# Electronic_Synchronized_Fireflies.net
KiCad netlist of a schematic drawn in EAGLE
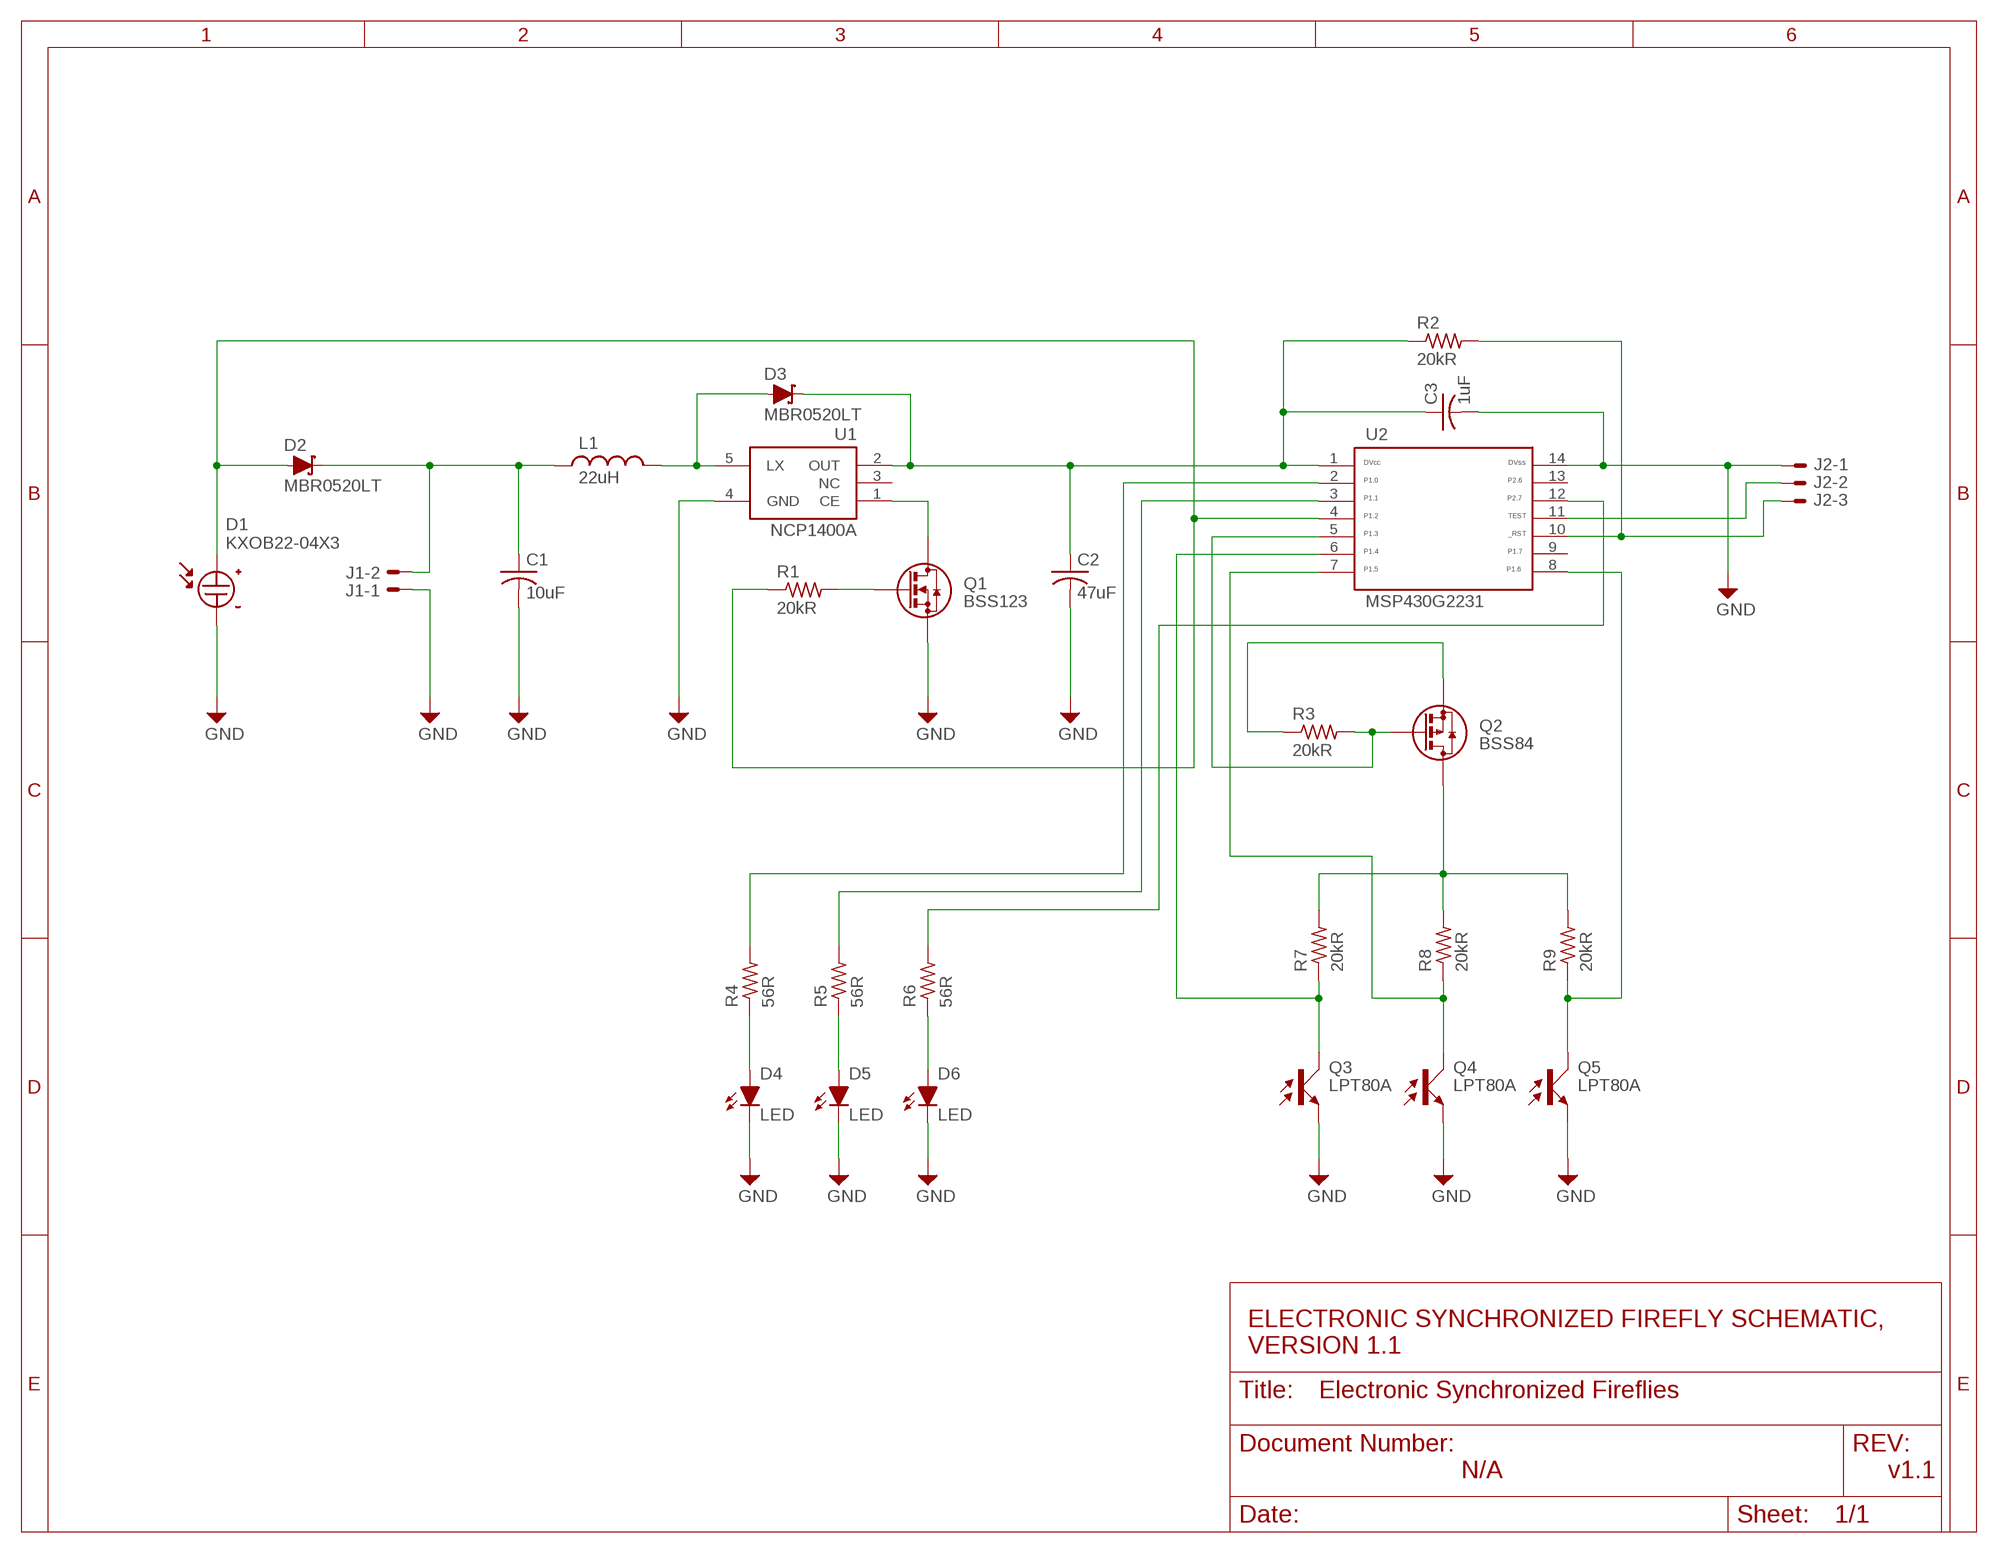
[diagram p0: schematic, sheet 1]

(export (version "E")
  (design (tool "Eeschema 10.0.6"))
  (components
    (comp (ref "C1")
      (value "10uF")
      (footprint "eagle-import:CAPACITOR_0805")
      (libsource (lib "eagle-import") (part "CAPACITOR"))
    )
    (comp (ref "C2")
      (value "47uF")
      (footprint "eagle-import:CAPACITOR_0805")
      (libsource (lib "eagle-import") (part "CAPACITOR"))
    )
    (comp (ref "C3")
      (value "1uF")
      (footprint "eagle-import:CAPACITOR_0805")
      (libsource (lib "eagle-import") (part "CAPACITOR"))
    )
    (comp (ref "D1")
      (value "KXOB22-04X3")
      (footprint "eagle-import:KXOB22-04X3")
      (libsource (lib "eagle-import") (part "KXOB22-04X3"))
    )
    (comp (ref "D2")
      (value "MBR0520LT")
      (footprint "eagle-import:SOD123")
      (libsource (lib "eagle-import") (part "MBR0520LT"))
    )
    (comp (ref "D3")
      (value "MBR0520LT")
      (footprint "eagle-import:SOD123")
      (libsource (lib "eagle-import") (part "MBR0520LT"))
    )
    (comp (ref "D4")
      (value "LED")
      (footprint "eagle-import:LED5MMRT")
      (libsource (lib "eagle-import") (part "LEDRTANGLEHOLDER"))
    )
    (comp (ref "D5")
      (value "LED")
      (footprint "eagle-import:LED5MMRT")
      (libsource (lib "eagle-import") (part "LEDRTANGLEHOLDER"))
    )
    (comp (ref "D6")
      (value "LED")
      (footprint "eagle-import:LED5MMRT")
      (libsource (lib "eagle-import") (part "LEDRTANGLEHOLDER"))
    )
    (comp (ref "FRAME1")
      (value "FRAME_A_L")
      (footprint "eagle-import:FRAME_A_L")
      (libsource (lib "eagle-import") (part "FRAME_A_L"))
    )
    (comp (ref "J1")
      (value "2WIRE_HEADER")
      (footprint "eagle-import:2WIRE_HEADER")
      (fields (field (name "MF") "MOLEX") (field (name "MPN") "22-23-2021"))
      (libsource (lib "eagle-import") (part "2WIRE_HEADER"))
    )
    (comp (ref "J2")
      (value "3WIRE_HEADER")
      (footprint "eagle-import:3WIRE_HEADER")
      (fields (field (name "MF") "MOLEX") (field (name "MPN") "22-23-2031"))
      (libsource (lib "eagle-import") (part "3WIRE_HEADER"))
    )
    (comp (ref "L1")
      (value "22uH")
      (footprint "eagle-import:INDUCTOR_1007")
      (libsource (lib "eagle-import") (part "INDUCTOR"))
    )
    (comp (ref "Q1")
      (value "BSS123")
      (footprint "eagle-import:SOT23")
      (libsource (lib "eagle-import") (part "BSS123"))
    )
    (comp (ref "Q2")
      (value "BSS84")
      (footprint "eagle-import:SOT23")
      (libsource (lib "eagle-import") (part "BSS84"))
    )
    (comp (ref "Q3")
      (value "LPT80A")
      (footprint "eagle-import:LED5MMRT")
      (libsource (lib "eagle-import") (part "LPT80ARTANGLEHOLDER"))
    )
    (comp (ref "Q4")
      (value "LPT80A")
      (footprint "eagle-import:LED5MMRT")
      (libsource (lib "eagle-import") (part "LPT80ARTANGLEHOLDER"))
    )
    (comp (ref "Q5")
      (value "LPT80A")
      (footprint "eagle-import:LED5MMRT")
      (libsource (lib "eagle-import") (part "LPT80ARTANGLEHOLDER"))
    )
    (comp (ref "R1")
      (value "20kR")
      (footprint "eagle-import:RESISTOR_0805")
      (libsource (lib "eagle-import") (part "RESISTOR"))
    )
    (comp (ref "R2")
      (value "20kR")
      (footprint "eagle-import:RESISTOR_0805")
      (libsource (lib "eagle-import") (part "RESISTOR"))
    )
    (comp (ref "R3")
      (value "20kR")
      (footprint "eagle-import:RESISTOR_0805")
      (libsource (lib "eagle-import") (part "RESISTOR"))
    )
    (comp (ref "R4")
      (value "56R")
      (footprint "eagle-import:RESISTOR_0805")
      (libsource (lib "eagle-import") (part "RESISTOR"))
    )
    (comp (ref "R5")
      (value "56R")
      (footprint "eagle-import:RESISTOR_0805")
      (libsource (lib "eagle-import") (part "RESISTOR"))
    )
    (comp (ref "R6")
      (value "56R")
      (footprint "eagle-import:RESISTOR_0805")
      (libsource (lib "eagle-import") (part "RESISTOR"))
    )
    (comp (ref "R7")
      (value "20kR")
      (footprint "eagle-import:RESISTOR_0805")
      (libsource (lib "eagle-import") (part "RESISTOR"))
    )
    (comp (ref "R8")
      (value "20kR")
      (footprint "eagle-import:RESISTOR_0805")
      (libsource (lib "eagle-import") (part "RESISTOR"))
    )
    (comp (ref "R9")
      (value "20kR")
      (footprint "eagle-import:RESISTOR_0805")
      (libsource (lib "eagle-import") (part "RESISTOR"))
    )
    (comp (ref "U$1")
      (value "DOCFIELD")
      (footprint "eagle-import:DOCFIELD")
      (libsource (lib "eagle-import") (part "DOCFIELD"))
    )
    (comp (ref "U1")
      (value "NCP1400A")
      (footprint "eagle-import:SOT23-5")
      (libsource (lib "eagle-import") (part "NCP1400A"))
    )
    (comp (ref "U2")
      (value "MSP430G2231")
      (footprint "eagle-import:TSSOP-14")
      (libsource (lib "eagle-import") (part "MSP430G2231"))
    )
  )
  (nets
    (net (code "1") (name "GND") (class "Default")
      (node (ref "C1") (pin "2") (pinfunction "2_2") (pintype "passive"))
      (node (ref "C2") (pin "2") (pinfunction "2_2") (pintype "passive"))
      (node (ref "C3") (pin "2") (pinfunction "2_2") (pintype "passive"))
      (node (ref "D1") (pin "P$2") (pinfunction "-_P$2") (pintype "passive"))
      (node (ref "D4") (pin "K") (pinfunction "C_K") (pintype "passive"))
      (node (ref "D5") (pin "K") (pinfunction "C_K") (pintype "passive"))
      (node (ref "D6") (pin "K") (pinfunction "C_K") (pintype "passive"))
      (node (ref "J1") (pin "1") (pinfunction "S_1") (pintype "passive"))
      (node (ref "J2") (pin "1") (pinfunction "S_1") (pintype "passive"))
      (node (ref "Q1") (pin "3") (pinfunction "D_3") (pintype "passive"))
      (node (ref "Q3") (pin "K") (pinfunction "E_K") (pintype "passive"))
      (node (ref "Q4") (pin "K") (pinfunction "E_K") (pintype "passive"))
      (node (ref "Q5") (pin "K") (pinfunction "E_K") (pintype "passive"))
      (node (ref "U1") (pin "4") (pinfunction "GND_4") (pintype "bidirectional"))
      (node (ref "U2") (pin "14") (pinfunction "14_14") (pintype "bidirectional"))
    )
    (net (code "2") (name "Net-(D1-+)") (class "Default")
      (node (ref "D1") (pin "P$1") (pinfunction "+_P$1") (pintype "passive"))
      (node (ref "D2") (pin "A") (pinfunction "A_A") (pintype "input"))
      (node (ref "R1") (pin "1") (pinfunction "P$1_1") (pintype "passive"))
      (node (ref "U2") (pin "4") (pinfunction "4_4") (pintype "bidirectional"))
    )
    (net (code "3") (name "Net-(J1B-S)") (class "Default")
      (node (ref "C1") (pin "1") (pinfunction "1_1") (pintype "passive"))
      (node (ref "D2") (pin "C") (pinfunction "C_C") (pintype "output"))
      (node (ref "J1") (pin "2") (pinfunction "S_2") (pintype "passive"))
      (node (ref "L1") (pin "P$1") (pinfunction "1_P$1") (pintype "passive"))
    )
    (net (code "4") (name "Net-(J2B-S)") (class "Default")
      (node (ref "J2") (pin "2") (pinfunction "S_2") (pintype "passive"))
      (node (ref "U2") (pin "11") (pinfunction "11_11") (pintype "bidirectional"))
    )
    (net (code "5") (name "Net-(J2C-S)") (class "Default")
      (node (ref "J2") (pin "3") (pinfunction "S_3") (pintype "passive"))
      (node (ref "R2") (pin "2") (pinfunction "P$2_2") (pintype "passive"))
      (node (ref "U2") (pin "10") (pinfunction "10_10") (pintype "bidirectional"))
    )
    (net (code "6") (name "Net-(L1-2)") (class "Default")
      (node (ref "D3") (pin "A") (pinfunction "A_A") (pintype "input"))
      (node (ref "L1") (pin "P$2") (pinfunction "2_P$2") (pintype "passive"))
      (node (ref "U1") (pin "5") (pinfunction "LX_5") (pintype "bidirectional"))
    )
    (net (code "7") (name "Net-(Q1-G)") (class "Default")
      (node (ref "Q1") (pin "1") (pinfunction "G_1") (pintype "passive"))
      (node (ref "R1") (pin "2") (pinfunction "P$2_2") (pintype "passive"))
    )
    (net (code "8") (name "Net-(Q1-S)") (class "Default")
      (node (ref "Q1") (pin "2") (pinfunction "S_2") (pintype "passive"))
      (node (ref "U1") (pin "1") (pinfunction "CE_1") (pintype "bidirectional"))
    )
    (net (code "9") (name "Net-(Q2-D)") (class "Default")
      (node (ref "Q2") (pin "3") (pinfunction "D_3") (pintype "passive"))
      (node (ref "R7") (pin "2") (pinfunction "P$2_2") (pintype "passive"))
      (node (ref "R8") (pin "2") (pinfunction "P$2_2") (pintype "passive"))
      (node (ref "R9") (pin "2") (pinfunction "P$2_2") (pintype "passive"))
    )
    (net (code "10") (name "Net-(Q2-G)") (class "Default")
      (node (ref "Q2") (pin "1") (pinfunction "G_1") (pintype "passive"))
      (node (ref "R3") (pin "2") (pinfunction "P$2_2") (pintype "passive"))
      (node (ref "U2") (pin "5") (pinfunction "5_5") (pintype "bidirectional"))
    )
    (net (code "11") (name "Net-(Q2-S)") (class "Default")
      (node (ref "Q2") (pin "2") (pinfunction "S_2") (pintype "passive"))
      (node (ref "R3") (pin "1") (pinfunction "P$1_1") (pintype "passive"))
    )
    (net (code "12") (name "Net-(Q3-C)") (class "Default")
      (node (ref "Q3") (pin "A") (pinfunction "C_A") (pintype "passive"))
      (node (ref "R7") (pin "1") (pinfunction "P$1_1") (pintype "passive"))
      (node (ref "U2") (pin "6") (pinfunction "6_6") (pintype "bidirectional"))
    )
    (net (code "13") (name "Net-(Q4-C)") (class "Default")
      (node (ref "Q4") (pin "A") (pinfunction "C_A") (pintype "passive"))
      (node (ref "R8") (pin "1") (pinfunction "P$1_1") (pintype "passive"))
      (node (ref "U2") (pin "7") (pinfunction "7_7") (pintype "bidirectional"))
    )
    (net (code "14") (name "Net-(Q5-C)") (class "Default")
      (node (ref "Q5") (pin "A") (pinfunction "C_A") (pintype "passive"))
      (node (ref "R9") (pin "1") (pinfunction "P$1_1") (pintype "passive"))
      (node (ref "U2") (pin "8") (pinfunction "8_8") (pintype "bidirectional"))
    )
    (net (code "15") (name "Net-(R2-P$1)") (class "Default")
      (node (ref "C2") (pin "1") (pinfunction "1_1") (pintype "passive"))
      (node (ref "C3") (pin "1") (pinfunction "1_1") (pintype "passive"))
      (node (ref "D3") (pin "C") (pinfunction "C_C") (pintype "output"))
      (node (ref "R2") (pin "1") (pinfunction "P$1_1") (pintype "passive"))
      (node (ref "U1") (pin "2") (pinfunction "OUT_2") (pintype "bidirectional"))
      (node (ref "U2") (pin "1") (pinfunction "1_1") (pintype "bidirectional"))
    )
    (net (code "16") (name "Net-(R4-P$1)") (class "Default")
      (node (ref "D4") (pin "A") (pinfunction "A_A") (pintype "passive"))
      (node (ref "R4") (pin "1") (pinfunction "P$1_1") (pintype "passive"))
    )
    (net (code "17") (name "Net-(R4-P$2)") (class "Default")
      (node (ref "R4") (pin "2") (pinfunction "P$2_2") (pintype "passive"))
      (node (ref "U2") (pin "2") (pinfunction "2_2") (pintype "bidirectional"))
    )
    (net (code "18") (name "Net-(R5-P$1)") (class "Default")
      (node (ref "D5") (pin "A") (pinfunction "A_A") (pintype "passive"))
      (node (ref "R5") (pin "1") (pinfunction "P$1_1") (pintype "passive"))
    )
    (net (code "19") (name "Net-(R5-P$2)") (class "Default")
      (node (ref "R5") (pin "2") (pinfunction "P$2_2") (pintype "passive"))
      (node (ref "U2") (pin "3") (pinfunction "3_3") (pintype "bidirectional"))
    )
    (net (code "20") (name "Net-(R6-P$1)") (class "Default")
      (node (ref "D6") (pin "A") (pinfunction "A_A") (pintype "passive"))
      (node (ref "R6") (pin "1") (pinfunction "P$1_1") (pintype "passive"))
    )
    (net (code "21") (name "Net-(R6-P$2)") (class "Default")
      (node (ref "R6") (pin "2") (pinfunction "P$2_2") (pintype "passive"))
      (node (ref "U2") (pin "12") (pinfunction "12_12") (pintype "bidirectional"))
    )
    (net (code "22") (name "unconnected-(U1-NC-Pad3)") (class "Default")
      (node (ref "U1") (pin "3") (pinfunction "NC_3") (pintype "bidirectional"))
    )
    (net (code "23") (name "unconnected-(U2-Pad9)") (class "Default")
      (node (ref "U2") (pin "9") (pinfunction "9_9") (pintype "bidirectional"))
    )
    (net (code "24") (name "unconnected-(U2-Pad13)") (class "Default")
      (node (ref "U2") (pin "13") (pinfunction "13_13") (pintype "bidirectional"))
    )
  )
)
